# Haptic_Motor_Driver_DRV2605L_v20.net
KiCad netlist of a schematic drawn in EAGLE
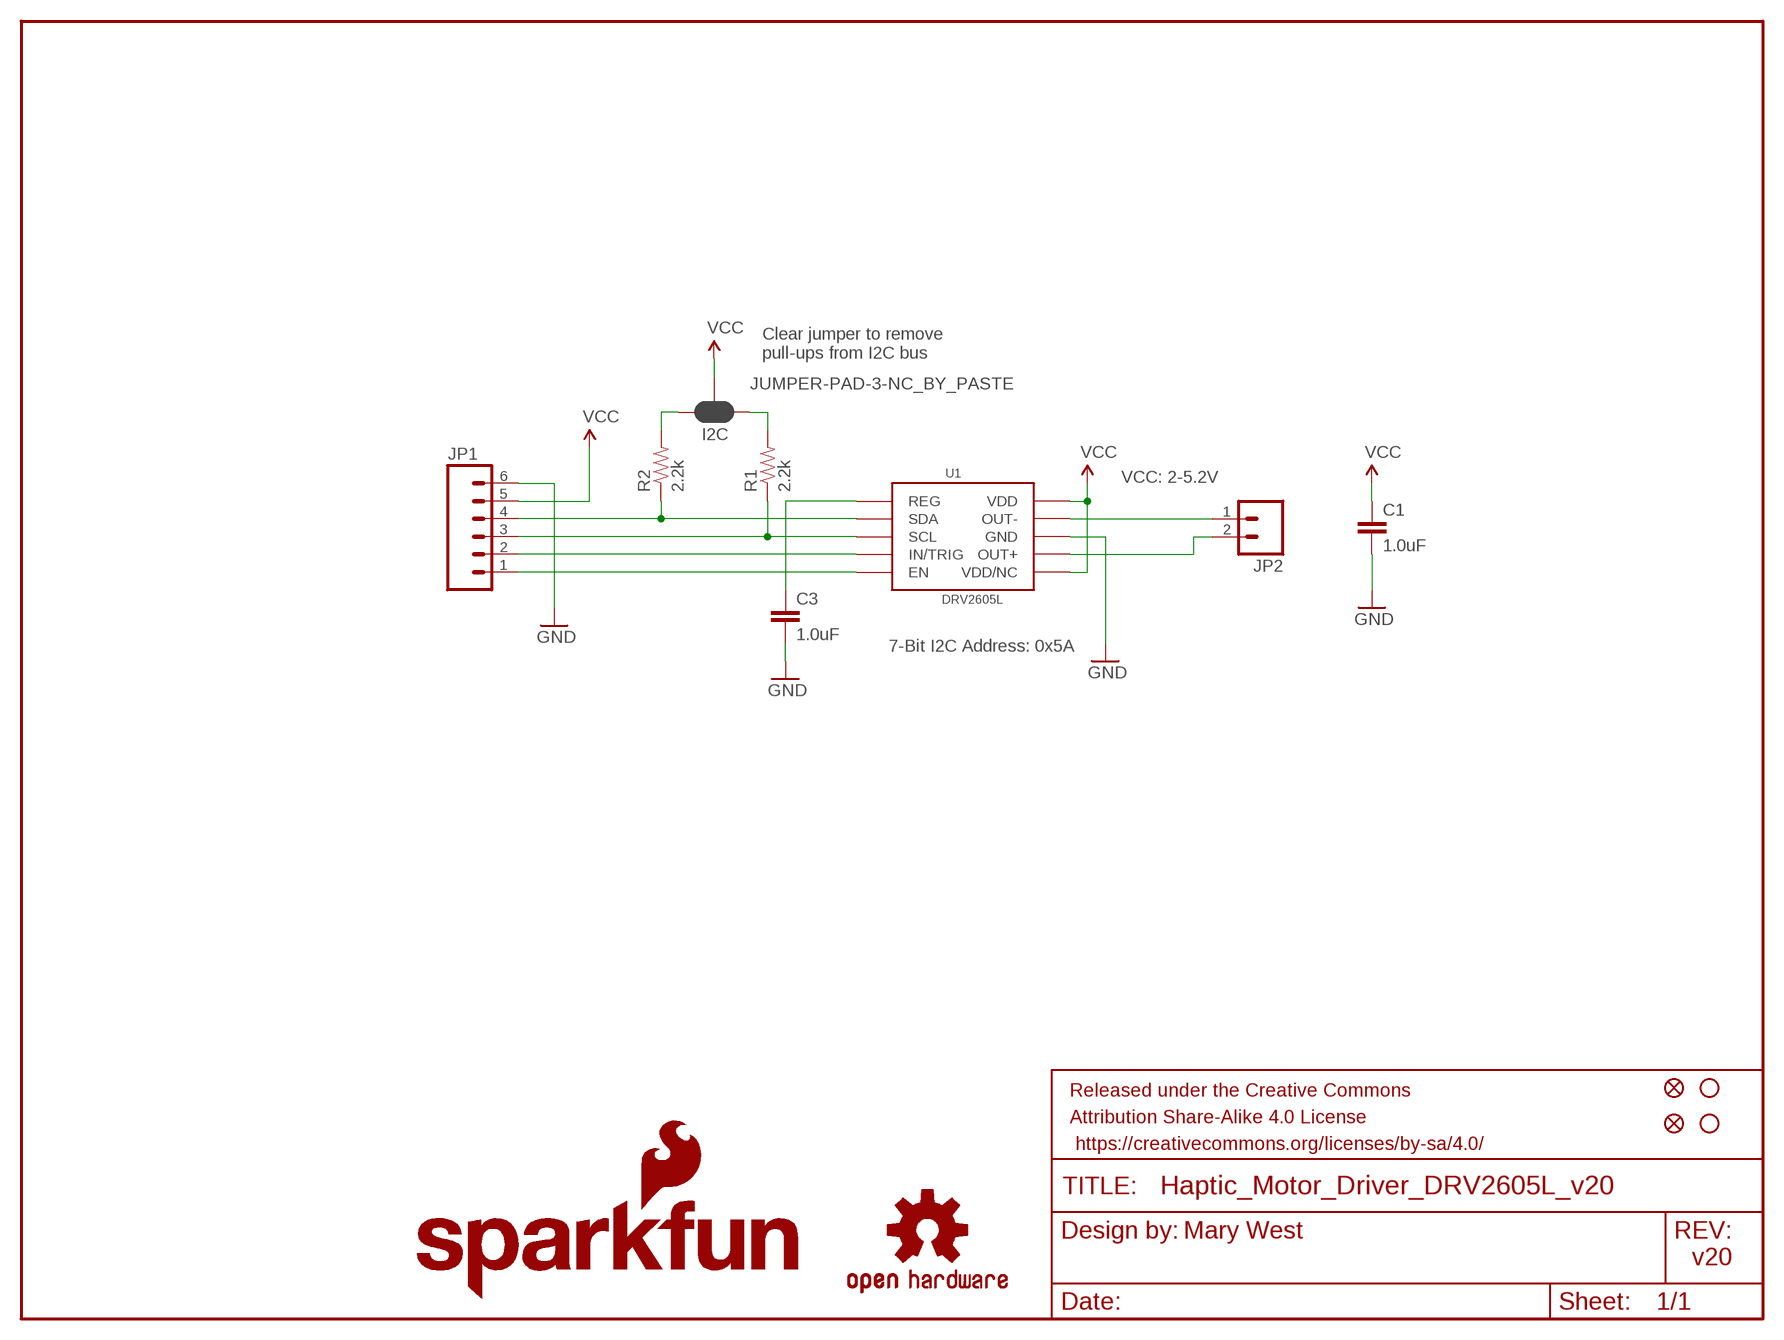
[diagram p0: schematic, sheet 1]

(export (version "E")
  (design (tool "Eeschema 10.0.6"))
  (components
    (comp (ref "C1")
      (value "1.0uF")
      (footprint "eagle-import:0402-CAP")
      (libsource (lib "eagle-import") (part "1.0UF-16V-10%(0402)"))
    )
    (comp (ref "C3")
      (value "1.0uF")
      (footprint "eagle-import:0402-CAP")
      (libsource (lib "eagle-import") (part "1.0UF-16V-10%(0402)"))
    )
    (comp (ref "FID1")
      (value "FIDUCIAL1X2")
      (footprint "eagle-import:FIDUCIAL-1X2")
      (libsource (lib "eagle-import") (part "FIDUCIAL1X2"))
    )
    (comp (ref "FID2")
      (value "FIDUCIAL1X2")
      (footprint "eagle-import:FIDUCIAL-1X2")
      (libsource (lib "eagle-import") (part "FIDUCIAL1X2"))
    )
    (comp (ref "FRAME2")
      (value "FRAME-LETTER")
      (footprint "eagle-import:CREATIVE_COMMONS")
      (libsource (lib "eagle-import") (part "FRAME-LETTER"))
    )
    (comp (ref "I2C")
      (value "JUMPER-PAD-3-NC_BY_PASTE")
      (footprint "eagle-import:PAD-JUMPER-3-NC_BY_PASTE_YES_SILK_FULL_BOX")
      (libsource (lib "eagle-import") (part "JUMPER-PAD-3-NC_BY_PASTE"))
    )
    (comp (ref "JP1")
      (value "M06SILK_FEMALE_PTH")
      (footprint "eagle-import:1X06")
      (libsource (lib "eagle-import") (part "M06SILK_FEMALE_PTH"))
    )
    (comp (ref "JP2")
      (value "M02PTH")
      (footprint "eagle-import:1X02")
      (libsource (lib "eagle-import") (part "M02PTH"))
    )
    (comp (ref "LOGO2")
      (value "OSHW-LOGOS")
      (footprint "eagle-import:OSHW-LOGO-S")
      (libsource (lib "eagle-import") (part "OSHW-LOGOS"))
    )
    (comp (ref "LOGO4")
      (value "SFE_LOGO_NAME_FLAME.1_INCH")
      (footprint "eagle-import:SFE_LOGO_NAME_FLAME_.1")
      (libsource (lib "eagle-import") (part "SFE_LOGO_NAME_FLAME.1_INCH"))
    )
    (comp (ref "R1")
      (value "2.2k")
      (footprint "eagle-import:0603-RES")
      (libsource (lib "eagle-import") (part "2.2KOHM-1/10W-1%(0603)"))
    )
    (comp (ref "R2")
      (value "2.2k")
      (footprint "eagle-import:0603-RES")
      (libsource (lib "eagle-import") (part "2.2KOHM-1/10W-1%(0603)"))
    )
    (comp (ref "STANDOFF1")
      (value "STAND-OFF")
      (footprint "eagle-import:STAND-OFF")
      (libsource (lib "eagle-import") (part "STAND-OFF"))
    )
    (comp (ref "STANDOFF4")
      (value "STAND-OFF")
      (footprint "eagle-import:STAND-OFF")
      (libsource (lib "eagle-import") (part "STAND-OFF"))
    )
    (comp (ref "U1")
      (value "DRV2605L")
      (footprint "eagle-import:VSSOP-10")
      (libsource (lib "eagle-import") (part "DRV2605L"))
    )
  )
  (nets
    (net (code "1") (name "GND") (class "Default")
      (node (ref "C1") (pin "2") (pinfunction "2_2") (pintype "passive"))
      (node (ref "C3") (pin "2") (pinfunction "2_2") (pintype "passive"))
      (node (ref "JP1") (pin "6") (pinfunction "6_6") (pintype "passive"))
      (node (ref "U1") (pin "P$8") (pinfunction "GND_P$8") (pintype "bidirectional"))
    )
    (net (code "2") (name "Net-(I2C-Pad1)") (class "Default")
      (node (ref "I2C") (pin "1") (pinfunction "1_1") (pintype "passive"))
      (node (ref "R1") (pin "2") (pinfunction "2_2") (pintype "passive"))
    )
    (net (code "3") (name "Net-(I2C-Pad3)") (class "Default")
      (node (ref "I2C") (pin "3") (pinfunction "3_3") (pintype "passive"))
      (node (ref "R2") (pin "2") (pinfunction "2_2") (pintype "passive"))
    )
    (net (code "4") (name "Net-(U1-EN)") (class "Default")
      (node (ref "JP1") (pin "1") (pinfunction "1_1") (pintype "passive"))
      (node (ref "U1") (pin "P$5") (pinfunction "EN_P$5") (pintype "bidirectional"))
    )
    (net (code "5") (name "Net-(U1-IN{slash}TRIG)") (class "Default")
      (node (ref "JP1") (pin "2") (pinfunction "2_2") (pintype "passive"))
      (node (ref "U1") (pin "P$4") (pinfunction "IN/TRIG_P$4") (pintype "bidirectional"))
    )
    (net (code "6") (name "Net-(U1-OUT+)") (class "Default")
      (node (ref "JP2") (pin "2") (pinfunction "2_2") (pintype "passive"))
      (node (ref "U1") (pin "P$7") (pinfunction "OUT+_P$7") (pintype "bidirectional"))
    )
    (net (code "7") (name "Net-(U1-OUT-)") (class "Default")
      (node (ref "JP2") (pin "1") (pinfunction "1_1") (pintype "passive"))
      (node (ref "U1") (pin "P$9") (pinfunction "OUT-_P$9") (pintype "bidirectional"))
    )
    (net (code "8") (name "Net-(U1-REG)") (class "Default")
      (node (ref "C3") (pin "1") (pinfunction "1_1") (pintype "passive"))
      (node (ref "U1") (pin "P$1") (pinfunction "REG_P$1") (pintype "bidirectional"))
    )
    (net (code "9") (name "Net-(U1-SCL)") (class "Default")
      (node (ref "JP1") (pin "3") (pinfunction "3_3") (pintype "passive"))
      (node (ref "R1") (pin "1") (pinfunction "1_1") (pintype "passive"))
      (node (ref "U1") (pin "P$2") (pinfunction "SCL_P$2") (pintype "bidirectional"))
    )
    (net (code "10") (name "Net-(U1-SDA)") (class "Default")
      (node (ref "JP1") (pin "4") (pinfunction "4_4") (pintype "passive"))
      (node (ref "R2") (pin "1") (pinfunction "1_1") (pintype "passive"))
      (node (ref "U1") (pin "P$3") (pinfunction "SDA_P$3") (pintype "bidirectional"))
    )
    (net (code "11") (name "VCC") (class "Default")
      (node (ref "C1") (pin "1") (pinfunction "1_1") (pintype "passive"))
      (node (ref "I2C") (pin "2") (pinfunction "2_2") (pintype "passive"))
      (node (ref "JP1") (pin "5") (pinfunction "5_5") (pintype "passive"))
      (node (ref "U1") (pin "P$10") (pinfunction "VDD_P$10") (pintype "bidirectional"))
      (node (ref "U1") (pin "P$6") (pinfunction "VDD/NC_P$6") (pintype "bidirectional"))
    )
  )
)
